# Motor_Control.net
KiCad netlist of a schematic drawn in Altium Designer
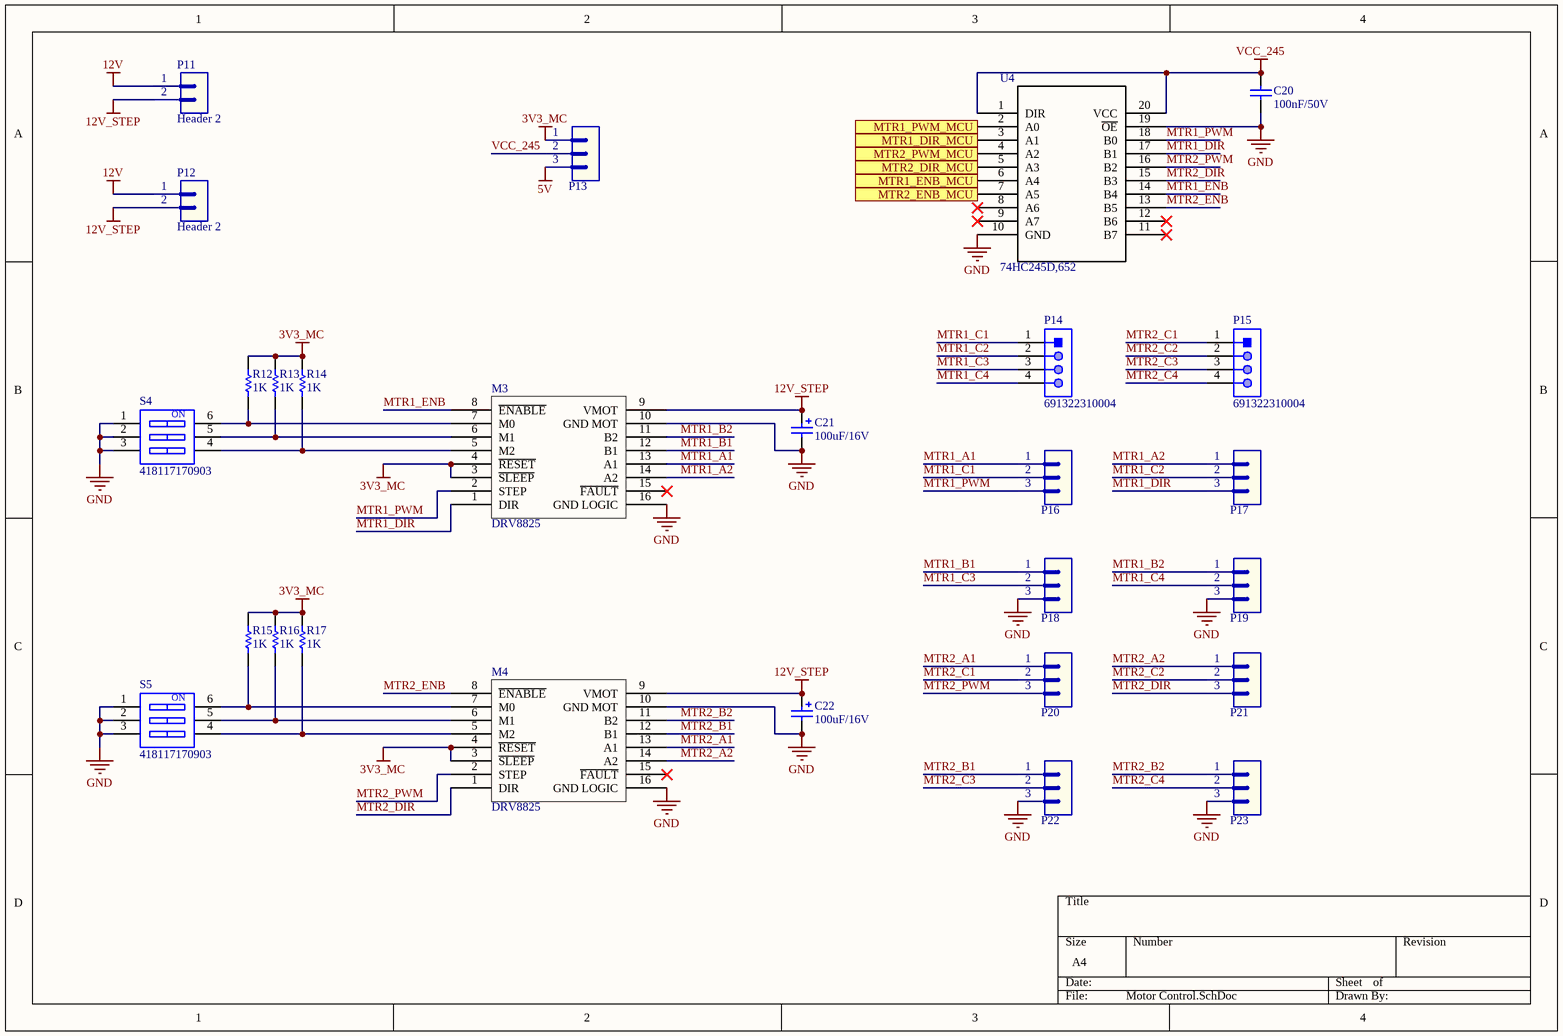
[diagram p0: Motor Control.SchDoc]

(export (version "E")
  (design (tool "Eeschema 10.0.6"))
  (components
    (comp (ref "C20")
      (value "100nF/50V")
      (footprint "CAP-SM-0805")
      (description "CAP CER 0.1UF 50V Y5V 0805")
      (fields
        (field (name "MANUFACTURER") "Samsung Electro-Mechanics")
        (field (name "MANUFACTURER PART NUMBER") "CL21F104ZBCNNNC")
      )
      (libsource (lib "Capacitor") (part "Cap-100nF-50V-0805"))
    )
    (comp (ref "C21")
      (value "100uF/16V")
      (footprint "CAP-SM-AL-SIZE-D-D6L6")
      (description "CAP ALUM 100UF 20% 16V SMD")
      (fields
        (field (name "MANUFACTURER") "Nichicon")
        (field (name "MANUFACTURER PART NUMBER") "UWX1C101MCL1GB")
      )
      (libsource (lib "Capacitor") (part "Cap-Al-100uF-16V-D6L5"))
    )
    (comp (ref "C22")
      (value "100uF/16V")
      (footprint "CAP-SM-AL-SIZE-D-D6L6")
      (description "CAP ALUM 100UF 20% 16V SMD")
      (fields
        (field (name "MANUFACTURER") "Nichicon")
        (field (name "MANUFACTURER PART NUMBER") "UWX1C101MCL1GB")
      )
      (libsource (lib "Capacitor") (part "Cap-Al-100uF-16V-D6L5"))
    )
    (comp (ref "M3") (value "DRV8825") (footprint "DRV8825") (libsource (lib "xecanbang") (part "DRV8825")))
    (comp (ref "M4") (value "DRV8825") (footprint "DRV8825") (libsource (lib "xecanbang") (part "DRV8825")))
    (comp (ref "P11")
      (value "Header 2")
      (footprint "JP2")
      (description "Header, 2-Pin")
      (fields (field (name "PUBLISHER") "Altium Limited"))
      (libsource (lib "Header-connector") (part "Header 2"))
    )
    (comp (ref "P12")
      (value "Header 2")
      (footprint "JP2")
      (description "Header, 2-Pin")
      (fields (field (name "PUBLISHER") "Altium Limited"))
      (libsource (lib "Header-connector") (part "Header 2"))
    )
    (comp (ref "P13")
      (value "Header 3")
      (footprint "JP3")
      (description "Header, 3-Pin")
      (fields (field (name "PUBLISHER") "Altium Limited"))
      (libsource (lib "Header-connector") (part "Header 3"))
    )
    (comp (ref "P14")
      (value "691322310004")
      (footprint "691322310004")
      (description "WR-TBL Serie 322 Horizontal PCB Header, Pluggable, pitch 3.81mm, 4p")
      (fields (field (name "PUBLISHER") "Wurth Elektronik"))
      (libsource (lib "691322310002.") (part "691322310004"))
    )
    (comp (ref "P15")
      (value "691322310004")
      (footprint "691322310004")
      (description "WR-TBL Serie 322 Horizontal PCB Header, Pluggable, pitch 3.81mm, 4p")
      (fields (field (name "PUBLISHER") "Wurth Elektronik"))
      (libsource (lib "691322310002.") (part "691322310004"))
    )
    (comp (ref "P16")
      (value "Header 3")
      (footprint "JP3")
      (description "Header, 3-Pin")
      (fields (field (name "PUBLISHER") "Altium Limited"))
      (libsource (lib "Header-connector") (part "Header 3"))
    )
    (comp (ref "P17")
      (value "Header 3")
      (footprint "JP3")
      (description "Header, 3-Pin")
      (fields (field (name "PUBLISHER") "Altium Limited"))
      (libsource (lib "Header-connector") (part "Header 3"))
    )
    (comp (ref "P18")
      (value "Header 3")
      (footprint "JP3")
      (description "Header, 3-Pin")
      (fields (field (name "PUBLISHER") "Altium Limited"))
      (libsource (lib "Header-connector") (part "Header 3"))
    )
    (comp (ref "P19")
      (value "Header 3")
      (footprint "JP3")
      (description "Header, 3-Pin")
      (fields (field (name "PUBLISHER") "Altium Limited"))
      (libsource (lib "Header-connector") (part "Header 3"))
    )
    (comp (ref "P20")
      (value "Header 3")
      (footprint "JP3")
      (description "Header, 3-Pin")
      (fields (field (name "PUBLISHER") "Altium Limited"))
      (libsource (lib "Header-connector") (part "Header 3"))
    )
    (comp (ref "P21")
      (value "Header 3")
      (footprint "JP3")
      (description "Header, 3-Pin")
      (fields (field (name "PUBLISHER") "Altium Limited"))
      (libsource (lib "Header-connector") (part "Header 3"))
    )
    (comp (ref "P22")
      (value "Header 3")
      (footprint "JP3")
      (description "Header, 3-Pin")
      (fields (field (name "PUBLISHER") "Altium Limited"))
      (libsource (lib "Header-connector") (part "Header 3"))
    )
    (comp (ref "P23")
      (value "Header 3")
      (footprint "JP3")
      (description "Header, 3-Pin")
      (fields (field (name "PUBLISHER") "Altium Limited"))
      (libsource (lib "Header-connector") (part "Header 3"))
    )
    (comp (ref "R12")
      (value "1K")
      (footprint "Resistor:RES-SM-0805")
      (description "RES 1K OHM 1% 1/4W 0805")
      (fields
        (field (name "MANUFACTURER") "Stackpole Electronics Inc")
        (field (name "MANUFACTURER PART NUMBER") "RNCP0805FTD1K00")
      )
      (libsource (lib "Resistor") (part "Res-1K-0805"))
    )
    (comp (ref "R13")
      (value "1K")
      (footprint "Resistor:RES-SM-0805")
      (description "RES 1K OHM 1% 1/4W 0805")
      (fields
        (field (name "MANUFACTURER") "Stackpole Electronics Inc")
        (field (name "MANUFACTURER PART NUMBER") "RNCP0805FTD1K00")
      )
      (libsource (lib "Resistor") (part "Res-1K-0805"))
    )
    (comp (ref "R14")
      (value "1K")
      (footprint "Resistor:RES-SM-0805")
      (description "RES 1K OHM 1% 1/4W 0805")
      (fields
        (field (name "MANUFACTURER") "Stackpole Electronics Inc")
        (field (name "MANUFACTURER PART NUMBER") "RNCP0805FTD1K00")
      )
      (libsource (lib "Resistor") (part "Res-1K-0805"))
    )
    (comp (ref "R15")
      (value "1K")
      (footprint "Resistor:RES-SM-0805")
      (description "RES 1K OHM 1% 1/4W 0805")
      (fields
        (field (name "MANUFACTURER") "Stackpole Electronics Inc")
        (field (name "MANUFACTURER PART NUMBER") "RNCP0805FTD1K00")
      )
      (libsource (lib "Resistor") (part "Res-1K-0805"))
    )
    (comp (ref "R16")
      (value "1K")
      (footprint "Resistor:RES-SM-0805")
      (description "RES 1K OHM 1% 1/4W 0805")
      (fields
        (field (name "MANUFACTURER") "Stackpole Electronics Inc")
        (field (name "MANUFACTURER PART NUMBER") "RNCP0805FTD1K00")
      )
      (libsource (lib "Resistor") (part "Res-1K-0805"))
    )
    (comp (ref "R17")
      (value "1K")
      (footprint "Resistor:RES-SM-0805")
      (description "RES 1K OHM 1% 1/4W 0805")
      (fields
        (field (name "MANUFACTURER") "Stackpole Electronics Inc")
        (field (name "MANUFACTURER PART NUMBER") "RNCP0805FTD1K00")
      )
      (libsource (lib "Resistor") (part "Res-1K-0805"))
    )
    (comp (ref "S4")
      (value "418117170903")
      (footprint "418117170903")
      (description "WS-DITV Compact THT Dip Switch, Flat Actuator, pitch 2.54mm, 3p")
      (fields (field (name "PUBLISHER") "Wurth Elektronik"))
      (libsource (lib "418117270903") (part "418117170903"))
    )
    (comp (ref "S5")
      (value "418117170903")
      (footprint "418117170903")
      (description "WS-DITV Compact THT Dip Switch, Flat Actuator, pitch 2.54mm, 3p")
      (fields (field (name "PUBLISHER") "Wurth Elektronik"))
      (libsource (lib "418117270903") (part "418117170903"))
    )
    (comp (ref "U4")
      (value "74HC245D,652")
      (footprint "74HC245D-652")
      (fields (field (name "COPYRIGHT") "Copyright (C) 2016 Accelerated Designs. All rights reserved"))
      (libsource (lib "xecanbang") (part "74HC245D,652"))
    )
  )
  (nets
    (net (code "1") (name "/MTR1_A1") (class "Default")
      (node (ref "M3") (pin "13") (pinfunction "A1_13") (pintype "passive"))
      (node (ref "P16") (pin "1") (pinfunction "1_1") (pintype "passive"))
    )
    (net (code "2") (name "/MTR1_A2") (class "Default")
      (node (ref "M3") (pin "14") (pinfunction "A2_14") (pintype "passive"))
      (node (ref "P17") (pin "1") (pinfunction "1_1") (pintype "passive"))
    )
    (net (code "3") (name "/MTR1_B1") (class "Default")
      (node (ref "M3") (pin "12") (pinfunction "B1_12") (pintype "passive"))
      (node (ref "P18") (pin "1") (pinfunction "1_1") (pintype "passive"))
    )
    (net (code "4") (name "/MTR1_B2") (class "Default")
      (node (ref "M3") (pin "11") (pinfunction "B2_11") (pintype "passive"))
      (node (ref "P19") (pin "1") (pinfunction "1_1") (pintype "passive"))
    )
    (net (code "5") (name "/MTR1_C1") (class "Default")
      (node (ref "P14") (pin "1") (pinfunction "1_1") (pintype "passive"))
      (node (ref "P16") (pin "2") (pinfunction "2_2") (pintype "passive"))
    )
    (net (code "6") (name "/MTR1_C2") (class "Default")
      (node (ref "P14") (pin "2") (pinfunction "2_2") (pintype "passive"))
      (node (ref "P17") (pin "2") (pinfunction "2_2") (pintype "passive"))
    )
    (net (code "7") (name "/MTR1_C3") (class "Default")
      (node (ref "P14") (pin "3") (pinfunction "3_3") (pintype "passive"))
      (node (ref "P18") (pin "2") (pinfunction "2_2") (pintype "passive"))
    )
    (net (code "8") (name "/MTR1_C4") (class "Default")
      (node (ref "P14") (pin "4") (pinfunction "4_4") (pintype "passive"))
      (node (ref "P19") (pin "2") (pinfunction "2_2") (pintype "passive"))
    )
    (net (code "9") (name "/MTR1_DIR") (class "Default")
      (node (ref "M3") (pin "1") (pinfunction "DIR_1") (pintype "passive"))
      (node (ref "P17") (pin "3") (pinfunction "3_3") (pintype "passive"))
      (node (ref "U4") (pin "17") (pinfunction "B1_17") (pintype "passive"))
    )
    (net (code "10") (name "/MTR1_DIR_MCU") (class "Default")
      (node (ref "U4") (pin "3") (pinfunction "A1_3") (pintype "passive"))
    )
    (net (code "11") (name "/MTR1_ENB") (class "Default")
      (node (ref "M3") (pin "8") (pinfunction "~{ENABLE}_8") (pintype "passive"))
      (node (ref "U4") (pin "14") (pinfunction "B4_14") (pintype "passive"))
    )
    (net (code "12") (name "/MTR1_ENB_MCU") (class "Default")
      (node (ref "U4") (pin "6") (pinfunction "A4_6") (pintype "passive"))
    )
    (net (code "13") (name "/MTR1_PWM") (class "Default")
      (node (ref "M3") (pin "2") (pinfunction "STEP_2") (pintype "passive"))
      (node (ref "P16") (pin "3") (pinfunction "3_3") (pintype "passive"))
      (node (ref "U4") (pin "18") (pinfunction "B0_18") (pintype "passive"))
    )
    (net (code "14") (name "/MTR1_PWM_MCU") (class "Default")
      (node (ref "U4") (pin "2") (pinfunction "A0_2") (pintype "passive"))
    )
    (net (code "15") (name "/MTR2_A1") (class "Default")
      (node (ref "M4") (pin "13") (pinfunction "A1_13") (pintype "passive"))
      (node (ref "P20") (pin "1") (pinfunction "1_1") (pintype "passive"))
    )
    (net (code "16") (name "/MTR2_A2") (class "Default")
      (node (ref "M4") (pin "14") (pinfunction "A2_14") (pintype "passive"))
      (node (ref "P21") (pin "1") (pinfunction "1_1") (pintype "passive"))
    )
    (net (code "17") (name "/MTR2_B1") (class "Default")
      (node (ref "M4") (pin "12") (pinfunction "B1_12") (pintype "passive"))
      (node (ref "P22") (pin "1") (pinfunction "1_1") (pintype "passive"))
    )
    (net (code "18") (name "/MTR2_B2") (class "Default")
      (node (ref "M4") (pin "11") (pinfunction "B2_11") (pintype "passive"))
      (node (ref "P23") (pin "1") (pinfunction "1_1") (pintype "passive"))
    )
    (net (code "19") (name "/MTR2_C1") (class "Default")
      (node (ref "P15") (pin "1") (pinfunction "1_1") (pintype "passive"))
      (node (ref "P20") (pin "2") (pinfunction "2_2") (pintype "passive"))
    )
    (net (code "20") (name "/MTR2_C2") (class "Default")
      (node (ref "P15") (pin "2") (pinfunction "2_2") (pintype "passive"))
      (node (ref "P21") (pin "2") (pinfunction "2_2") (pintype "passive"))
    )
    (net (code "21") (name "/MTR2_C3") (class "Default")
      (node (ref "P15") (pin "3") (pinfunction "3_3") (pintype "passive"))
      (node (ref "P22") (pin "2") (pinfunction "2_2") (pintype "passive"))
    )
    (net (code "22") (name "/MTR2_C4") (class "Default")
      (node (ref "P15") (pin "4") (pinfunction "4_4") (pintype "passive"))
      (node (ref "P23") (pin "2") (pinfunction "2_2") (pintype "passive"))
    )
    (net (code "23") (name "/MTR2_DIR") (class "Default")
      (node (ref "M4") (pin "1") (pinfunction "DIR_1") (pintype "passive"))
      (node (ref "P21") (pin "3") (pinfunction "3_3") (pintype "passive"))
      (node (ref "U4") (pin "15") (pinfunction "B3_15") (pintype "passive"))
    )
    (net (code "24") (name "/MTR2_DIR_MCU") (class "Default")
      (node (ref "U4") (pin "5") (pinfunction "A3_5") (pintype "passive"))
    )
    (net (code "25") (name "/MTR2_ENB") (class "Default")
      (node (ref "M4") (pin "8") (pinfunction "~{ENABLE}_8") (pintype "passive"))
      (node (ref "U4") (pin "13") (pinfunction "B5_13") (pintype "passive"))
    )
    (net (code "26") (name "/MTR2_ENB_MCU") (class "Default")
      (node (ref "U4") (pin "7") (pinfunction "A5_7") (pintype "passive"))
    )
    (net (code "27") (name "/MTR2_PWM") (class "Default")
      (node (ref "M4") (pin "2") (pinfunction "STEP_2") (pintype "passive"))
      (node (ref "P20") (pin "3") (pinfunction "3_3") (pintype "passive"))
      (node (ref "U4") (pin "16") (pinfunction "B2_16") (pintype "passive"))
    )
    (net (code "28") (name "/MTR2_PWM_MCU") (class "Default")
      (node (ref "U4") (pin "4") (pinfunction "A2_4") (pintype "passive"))
    )
    (net (code "29") (name "3V3_MC") (class "Default")
      (node (ref "M3") (pin "3") (pinfunction "~{SLEEP}_3") (pintype "passive"))
      (node (ref "M3") (pin "4") (pinfunction "~{RESET}_4") (pintype "passive"))
      (node (ref "M4") (pin "3") (pinfunction "~{SLEEP}_3") (pintype "passive"))
      (node (ref "M4") (pin "4") (pinfunction "~{RESET}_4") (pintype "passive"))
      (node (ref "P13") (pin "1") (pinfunction "1_1") (pintype "passive"))
      (node (ref "R12") (pin "2") (pinfunction "2_2") (pintype "passive"))
      (node (ref "R13") (pin "2") (pinfunction "2_2") (pintype "passive"))
      (node (ref "R14") (pin "2") (pinfunction "2_2") (pintype "passive"))
      (node (ref "R15") (pin "2") (pinfunction "2_2") (pintype "passive"))
      (node (ref "R16") (pin "2") (pinfunction "2_2") (pintype "passive"))
      (node (ref "R17") (pin "2") (pinfunction "2_2") (pintype "passive"))
    )
    (net (code "30") (name "5V") (class "Default")
      (node (ref "P13") (pin "3") (pinfunction "3_3") (pintype "passive"))
    )
    (net (code "31") (name "12V") (class "Default")
      (node (ref "P11") (pin "1") (pinfunction "1_1") (pintype "passive"))
      (node (ref "P12") (pin "1") (pinfunction "1_1") (pintype "passive"))
    )
    (net (code "32") (name "12V_STEP") (class "Default")
      (node (ref "C21") (pin "1") (pinfunction "1_1") (pintype "passive"))
      (node (ref "C22") (pin "1") (pinfunction "1_1") (pintype "passive"))
      (node (ref "M3") (pin "9") (pinfunction "VMOT_9") (pintype "passive"))
      (node (ref "M4") (pin "9") (pinfunction "VMOT_9") (pintype "passive"))
      (node (ref "P11") (pin "2") (pinfunction "2_2") (pintype "passive"))
      (node (ref "P12") (pin "2") (pinfunction "2_2") (pintype "passive"))
    )
    (net (code "33") (name "GND") (class "Default")
      (node (ref "C20") (pin "1") (pinfunction "1_1") (pintype "passive"))
      (node (ref "C21") (pin "2") (pinfunction "2_2") (pintype "passive"))
      (node (ref "C22") (pin "2") (pinfunction "2_2") (pintype "passive"))
      (node (ref "M3") (pin "10") (pinfunction "GND_MOT_10") (pintype "passive"))
      (node (ref "M3") (pin "16") (pinfunction "GND_LOGIC_16") (pintype "passive"))
      (node (ref "M4") (pin "10") (pinfunction "GND_MOT_10") (pintype "passive"))
      (node (ref "M4") (pin "16") (pinfunction "GND_LOGIC_16") (pintype "passive"))
      (node (ref "P18") (pin "3") (pinfunction "3_3") (pintype "passive"))
      (node (ref "P19") (pin "3") (pinfunction "3_3") (pintype "passive"))
      (node (ref "P22") (pin "3") (pinfunction "3_3") (pintype "passive"))
      (node (ref "P23") (pin "3") (pinfunction "3_3") (pintype "passive"))
      (node (ref "S4") (pin "1") (pinfunction "1_1") (pintype "passive"))
      (node (ref "S4") (pin "2") (pinfunction "2_2") (pintype "passive"))
      (node (ref "S4") (pin "3") (pinfunction "3_3") (pintype "passive"))
      (node (ref "S5") (pin "1") (pinfunction "1_1") (pintype "passive"))
      (node (ref "S5") (pin "2") (pinfunction "2_2") (pintype "passive"))
      (node (ref "S5") (pin "3") (pinfunction "3_3") (pintype "passive"))
      (node (ref "U4") (pin "10") (pinfunction "GND_10") (pintype "passive"))
      (node (ref "U4") (pin "19") (pinfunction "~{OE}_19") (pintype "passive"))
    )
    (net (code "34") (name "Net-(M3-M0)") (class "Default")
      (node (ref "M3") (pin "7") (pinfunction "M0_7") (pintype "passive"))
      (node (ref "R12") (pin "1") (pinfunction "1_1") (pintype "passive"))
      (node (ref "S4") (pin "6") (pinfunction "6_6") (pintype "passive"))
    )
    (net (code "35") (name "Net-(M3-M1)") (class "Default")
      (node (ref "M3") (pin "6") (pinfunction "M1_6") (pintype "passive"))
      (node (ref "R13") (pin "1") (pinfunction "1_1") (pintype "passive"))
      (node (ref "S4") (pin "5") (pinfunction "5_5") (pintype "passive"))
    )
    (net (code "36") (name "Net-(M3-M2)") (class "Default")
      (node (ref "M3") (pin "5") (pinfunction "M2_5") (pintype "passive"))
      (node (ref "R14") (pin "1") (pinfunction "1_1") (pintype "passive"))
      (node (ref "S4") (pin "4") (pinfunction "4_4") (pintype "passive"))
    )
    (net (code "37") (name "Net-(M4-M0)") (class "Default")
      (node (ref "M4") (pin "7") (pinfunction "M0_7") (pintype "passive"))
      (node (ref "R15") (pin "1") (pinfunction "1_1") (pintype "passive"))
      (node (ref "S5") (pin "6") (pinfunction "6_6") (pintype "passive"))
    )
    (net (code "38") (name "Net-(M4-M1)") (class "Default")
      (node (ref "M4") (pin "6") (pinfunction "M1_6") (pintype "passive"))
      (node (ref "R16") (pin "1") (pinfunction "1_1") (pintype "passive"))
      (node (ref "S5") (pin "5") (pinfunction "5_5") (pintype "passive"))
    )
    (net (code "39") (name "Net-(M4-M2)") (class "Default")
      (node (ref "M4") (pin "5") (pinfunction "M2_5") (pintype "passive"))
      (node (ref "R17") (pin "1") (pinfunction "1_1") (pintype "passive"))
      (node (ref "S5") (pin "4") (pinfunction "4_4") (pintype "passive"))
    )
    (net (code "40") (name "VCC_245") (class "Default")
      (node (ref "C20") (pin "2") (pinfunction "2_2") (pintype "passive"))
      (node (ref "P13") (pin "2") (pinfunction "2_2") (pintype "passive"))
      (node (ref "U4") (pin "1") (pinfunction "DIR_1") (pintype "passive"))
      (node (ref "U4") (pin "20") (pinfunction "VCC_20") (pintype "passive"))
    )
    (net (code "41") (name "unconnected-(M3-~{FAULT}-Pad15)") (class "Default")
      (node (ref "M3") (pin "15") (pinfunction "~{FAULT}_15") (pintype "passive+no_connect"))
    )
    (net (code "42") (name "unconnected-(M4-~{FAULT}-Pad15)") (class "Default")
      (node (ref "M4") (pin "15") (pinfunction "~{FAULT}_15") (pintype "passive+no_connect"))
    )
    (net (code "43") (name "unconnected-(U4-A6-Pad8)") (class "Default")
      (node (ref "U4") (pin "8") (pinfunction "A6_8") (pintype "passive+no_connect"))
    )
    (net (code "44") (name "unconnected-(U4-A7-Pad9)") (class "Default")
      (node (ref "U4") (pin "9") (pinfunction "A7_9") (pintype "passive+no_connect"))
    )
    (net (code "45") (name "unconnected-(U4-B6-Pad12)") (class "Default")
      (node (ref "U4") (pin "12") (pinfunction "B6_12") (pintype "passive+no_connect"))
    )
    (net (code "46") (name "unconnected-(U4-B7-Pad11)") (class "Default")
      (node (ref "U4") (pin "11") (pinfunction "B7_11") (pintype "passive+no_connect"))
    )
  )
)
